# A-Main.net
KiCad netlist of a schematic drawn in Altium Designer
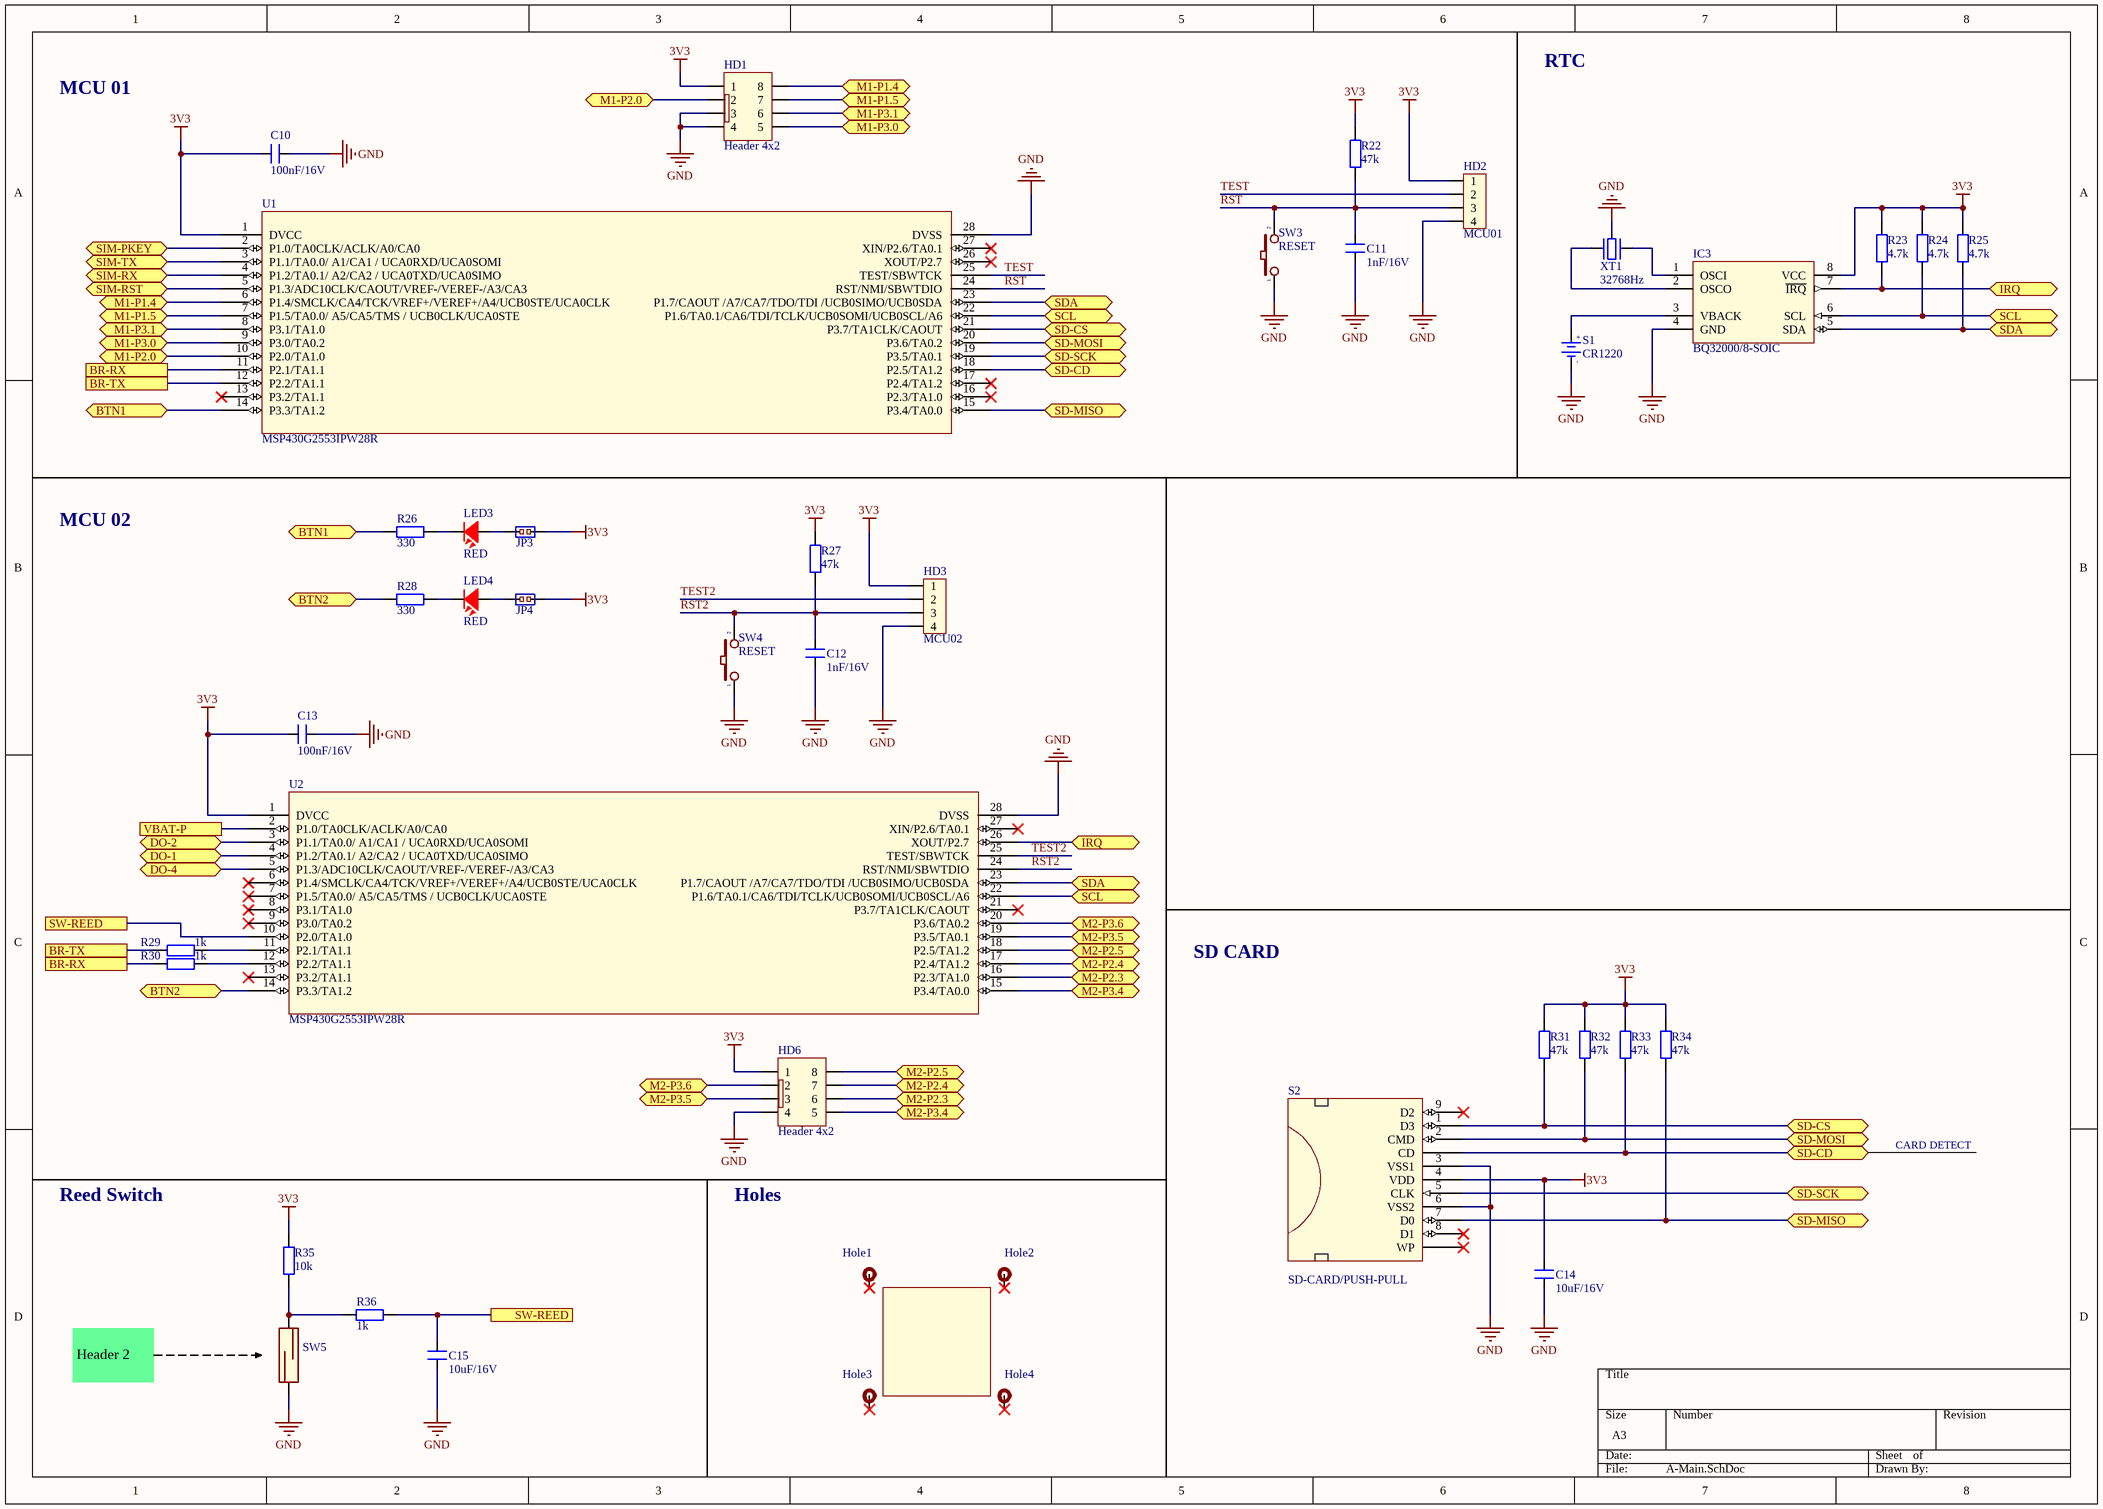
[diagram p0: A-Main.SchDoc]

(export (version "E")
  (design (tool "Eeschema 10.0.6"))
  (components
    (comp (ref "C10")
      (value "100nF/16V")
      (footprint "C0805-2012")
      (description "CAP CER 0.1UF 16V X7R 0805")
      (fields
        (field (name "MANUFACTURER") "Kemet")
        (field (name "MANUFACTURER PART NUMBER") "C0805C104K4RACTU")
      )
      (libsource (lib "Tran Tuan") (part "CAP-CER/100nF/16V/X7R/0805"))
    )
    (comp (ref "C11")
      (value "1nF/16V")
      (footprint "C0603-1608")
      (description "CAP CER 1000PF 16V X7R 0603")
      (fields
        (field (name "MANUFACTURER") "AVX Corporation")
        (field (name "MANUFACTURER PART NUMBER") "0603YC102KAT2A")
      )
      (libsource (lib "Tran Tuan") (part "CAP-CER/1nF/16V/X7R/0603"))
    )
    (comp (ref "C12")
      (value "1nF/16V")
      (footprint "C0603-1608")
      (description "CAP CER 1000PF 16V X7R 0603")
      (fields
        (field (name "MANUFACTURER") "AVX Corporation")
        (field (name "MANUFACTURER PART NUMBER") "0603YC102KAT2A")
      )
      (libsource (lib "Tran Tuan") (part "CAP-CER/1nF/16V/X7R/0603"))
    )
    (comp (ref "C13")
      (value "100nF/16V")
      (footprint "C0805-2012")
      (description "CAP CER 0.1UF 16V X7R 0805")
      (fields
        (field (name "MANUFACTURER") "Kemet")
        (field (name "MANUFACTURER PART NUMBER") "C0805C104K4RACTU")
      )
      (libsource (lib "Tran Tuan") (part "CAP-CER/100nF/16V/X7R/0805"))
    )
    (comp (ref "C14")
      (value "10uF/16V")
      (footprint "C0805-2012")
      (description "CAP CER 10UF 16V X5R 0805")
      (fields
        (field (name "MANUFACTURER") "Murata Electronics North America")
        (field (name "MANUFACTURER PART NUMBER") "GRM21BR61C106KE15L")
      )
      (libsource (lib "Tran Tuan") (part "CAP-CER/10UF/16V/X5R/0805"))
    )
    (comp (ref "C15")
      (value "10uF/16V")
      (footprint "C0805-2012")
      (description "CAP CER 10UF 16V X5R 0805")
      (fields
        (field (name "MANUFACTURER") "Murata Electronics North America")
        (field (name "MANUFACTURER PART NUMBER") "GRM21BR61C106KE15L")
      )
      (libsource (lib "Tran Tuan") (part "CAP-CER/10UF/16V/X5R/0805"))
    )
    (comp (ref "HD1")
      (value "Header 4x2")
      (footprint "HeaderSP_4x2")
      (description "HEADER, 4X2, 2.54MM, MALE")
      (libsource (lib "Tran Tuan") (part "HED-4X2/MALE/2.54MM-B"))
    )
    (comp (ref "HD2")
      (value "MCU01")
      (footprint "Header_4")
      (description "Header 4")
      (libsource (lib "Tran Tuan") (part "Hed4"))
    )
    (comp (ref "HD3")
      (value "MCU02")
      (footprint "Header_4")
      (description "Header 4")
      (libsource (lib "Tran Tuan") (part "Hed4"))
    )
    (comp (ref "HD6")
      (value "Header 4x2")
      (footprint "HeaderSP_4x2")
      (description "HEADER, 4X2, 2.54MM, MALE")
      (libsource (lib "Tran Tuan") (part "HED-4X2/MALE/2.54MM-B"))
    )
    (comp (ref "Hole1")
      (value "Pad Big")
      (footprint "Screw 3.0")
      (libsource (lib "Tran Tuan") (part "Pad_Big"))
    )
    (comp (ref "Hole2")
      (value "Pad Big")
      (footprint "Screw 3.0")
      (libsource (lib "Tran Tuan") (part "Pad_Big"))
    )
    (comp (ref "Hole3")
      (value "Pad Big")
      (footprint "Screw 3.0")
      (libsource (lib "Tran Tuan") (part "Pad_Big"))
    )
    (comp (ref "Hole4")
      (value "Pad Big")
      (footprint "Screw 3.0")
      (libsource (lib "Tran Tuan") (part "Pad_Big"))
    )
    (comp (ref "IC3")
      (value "BQ32000/8-SOIC")
      (footprint "RTC-BQ32000")
      (description "IC RTC CLK/CALENDAR I2C 8-SOIC")
      (fields
        (field (name "MANUFACTURER") "Texas Instruments")
        (field (name "MANUFACTURER PART NUMBER") "BQ32000DR")
      )
      (libsource (lib "Tran Tuan") (part "BQ32000/8-SOIC"))
    )
    (comp (ref "JP3")
      (value "JP2-ShortingJumper")
      (footprint "Header_2")
      (description "2.54mm 2-Pin Shorting Jumper")
      (libsource (lib "Tran Tuan") (part "JP2-ShortingJumper"))
    )
    (comp (ref "JP4")
      (value "JP2-ShortingJumper")
      (footprint "Header_2")
      (description "2.54mm 2-Pin Shorting Jumper")
      (libsource (lib "Tran Tuan") (part "JP2-ShortingJumper"))
    )
    (comp (ref "LED3")
      (value "RED")
      (footprint "Led 0805R")
      (description "LED RED CLEAR 0805 SMD")
      (fields
        (field (name "MANUFACTURER") "Lite-On Inc.")
        (field (name "MANUFACTURER PART NUMBER") "LTST-C171KRKT")
      )
      (libsource (lib "Tran Tuan") (part "LED-RED/CLEAR/0805"))
    )
    (comp (ref "LED4")
      (value "RED")
      (footprint "Led 0805R")
      (description "LED RED CLEAR 0805 SMD")
      (fields
        (field (name "MANUFACTURER") "Lite-On Inc.")
        (field (name "MANUFACTURER PART NUMBER") "LTST-C171KRKT")
      )
      (libsource (lib "Tran Tuan") (part "LED-RED/CLEAR/0805"))
    )
    (comp (ref "R22")
      (value "~")
      (footprint "RESC2012(0805)")
      (description "RES SMD 47K OHM 5% 1/8W 0805")
      (fields
        (field (name "MANUFACTURER") "Yageo")
        (field (name "MANUFACTURER PART NUMBER") "RC0805JR-0747KL")
        (field (name "RESISTANCE (OHMS)") "47k")
      )
      (libsource (lib "Tran Tuan") (part "RES-0805/±5%"))
    )
    (comp (ref "R23")
      (value "~")
      (footprint "RESC2012(0805)")
      (description "RES SMD 4.7K OHM 5% 1/8W 0805")
      (fields
        (field (name "MANUFACTURER") "Yageo")
        (field (name "MANUFACTURER PART NUMBER") "RC0805JR-074K7L")
        (field (name "RESISTANCE (OHMS)") "4.7k")
      )
      (libsource (lib "Tran Tuan") (part "RES-0805/±5%"))
    )
    (comp (ref "R24")
      (value "~")
      (footprint "RESC2012(0805)")
      (description "RES SMD 4.7K OHM 5% 1/8W 0805")
      (fields
        (field (name "MANUFACTURER") "Yageo")
        (field (name "MANUFACTURER PART NUMBER") "RC0805JR-074K7L")
        (field (name "RESISTANCE (OHMS)") "4.7k")
      )
      (libsource (lib "Tran Tuan") (part "RES-0805/±5%"))
    )
    (comp (ref "R25")
      (value "~")
      (footprint "RESC2012(0805)")
      (description "RES SMD 4.7K OHM 5% 1/8W 0805")
      (fields
        (field (name "MANUFACTURER") "Yageo")
        (field (name "MANUFACTURER PART NUMBER") "RC0805JR-074K7L")
        (field (name "RESISTANCE (OHMS)") "4.7k")
      )
      (libsource (lib "Tran Tuan") (part "RES-0805/±5%"))
    )
    (comp (ref "R26")
      (value "~")
      (footprint "RESC2012(0805)")
      (description "RES SMD 330 OHM 5% 1/8W 0805")
      (fields
        (field (name "MANUFACTURER") "Yageo")
        (field (name "MANUFACTURER PART NUMBER") "RC0805JR-07330RL")
        (field (name "RESISTANCE (OHMS)") "330")
      )
      (libsource (lib "") (part "RES-0805/±5%_1"))
    )
    (comp (ref "R27")
      (value "~")
      (footprint "RESC2012(0805)")
      (description "RES SMD 47K OHM 5% 1/8W 0805")
      (fields
        (field (name "MANUFACTURER") "Yageo")
        (field (name "MANUFACTURER PART NUMBER") "RC0805JR-0747KL")
        (field (name "RESISTANCE (OHMS)") "47k")
      )
      (libsource (lib "Tran Tuan") (part "RES-0805/±5%"))
    )
    (comp (ref "R28")
      (value "~")
      (footprint "RESC2012(0805)")
      (description "RES SMD 330 OHM 5% 1/8W 0805")
      (fields
        (field (name "MANUFACTURER") "Yageo")
        (field (name "MANUFACTURER PART NUMBER") "RC0805JR-07330RL")
        (field (name "RESISTANCE (OHMS)") "330")
      )
      (libsource (lib "") (part "RES-0805/±5%_1"))
    )
    (comp (ref "R29")
      (value "~")
      (footprint "RESC2012(0805)")
      (description "RES SMD 1K OHM 5% 1/8W 0805")
      (fields
        (field (name "MANUFACTURER") "Yageo")
        (field (name "MANUFACTURER PART NUMBER") "RC0805JR-071KL")
        (field (name "RESISTANCE (OHMS)") "1k")
      )
      (libsource (lib "") (part "RES-0805/±5%_1"))
    )
    (comp (ref "R30")
      (value "~")
      (footprint "RESC2012(0805)")
      (description "RES SMD 1K OHM 5% 1/8W 0805")
      (fields
        (field (name "MANUFACTURER") "Yageo")
        (field (name "MANUFACTURER PART NUMBER") "RC0805JR-071KL")
        (field (name "RESISTANCE (OHMS)") "1k")
      )
      (libsource (lib "") (part "RES-0805/±5%_1"))
    )
    (comp (ref "R31")
      (value "~")
      (footprint "RESC2012(0805)")
      (description "RES SMD 47K OHM 5% 1/8W 0805")
      (fields
        (field (name "MANUFACTURER") "Yageo")
        (field (name "MANUFACTURER PART NUMBER") "RC0805JR-0747KL")
        (field (name "RESISTANCE (OHMS)") "47k")
      )
      (libsource (lib "Tran Tuan") (part "RES-0805/±5%"))
    )
    (comp (ref "R32")
      (value "~")
      (footprint "RESC2012(0805)")
      (description "RES SMD 47K OHM 5% 1/8W 0805")
      (fields
        (field (name "MANUFACTURER") "Yageo")
        (field (name "MANUFACTURER PART NUMBER") "RC0805JR-0747KL")
        (field (name "RESISTANCE (OHMS)") "47k")
      )
      (libsource (lib "Tran Tuan") (part "RES-0805/±5%"))
    )
    (comp (ref "R33")
      (value "~")
      (footprint "RESC2012(0805)")
      (description "RES SMD 47K OHM 5% 1/8W 0805")
      (fields
        (field (name "MANUFACTURER") "Yageo")
        (field (name "MANUFACTURER PART NUMBER") "RC0805JR-0747KL")
        (field (name "RESISTANCE (OHMS)") "47k")
      )
      (libsource (lib "Tran Tuan") (part "RES-0805/±5%"))
    )
    (comp (ref "R34")
      (value "~")
      (footprint "RESC2012(0805)")
      (description "RES SMD 47K OHM 5% 1/8W 0805")
      (fields
        (field (name "MANUFACTURER") "Yageo")
        (field (name "MANUFACTURER PART NUMBER") "RC0805JR-0747KL")
        (field (name "RESISTANCE (OHMS)") "47k")
      )
      (libsource (lib "Tran Tuan") (part "RES-0805/±5%"))
    )
    (comp (ref "R35")
      (value "~")
      (footprint "RESC2012(0805)")
      (description "RES SMD 10K OHM 5% 1/8W 0805")
      (fields
        (field (name "MANUFACTURER") "Yageo")
        (field (name "MANUFACTURER PART NUMBER") "RC0805JR-0710KL")
        (field (name "RESISTANCE (OHMS)") "10k")
      )
      (libsource (lib "") (part "RES-0805/±5%_2"))
    )
    (comp (ref "R36")
      (value "~")
      (footprint "RESC2012(0805)")
      (description "RES SMD 1K OHM 5% 1/8W 0805")
      (fields
        (field (name "MANUFACTURER") "Yageo")
        (field (name "MANUFACTURER PART NUMBER") "RC0805JR-071KL")
        (field (name "RESISTANCE (OHMS)") "1k")
      )
      (libsource (lib "") (part "RES-0805/±5%_1"))
    )
    (comp (ref "S1")
      (value "CR1220")
      (footprint "Socket-PIN-BC501SM-TR")
      (description "CR1220 Battery Holder SMD")
      (fields (field (name "Comment") "BAT-HOLDER/CR1220/TME"))
      (libsource (lib "Tran Tuan") (part "BAT-HOLDER/CR1220/TME"))
    )
    (comp (ref "S2")
      (value "SD-CARD/PUSH-PULL")
      (footprint "SD-CARD")
      (description "CONN SD CARD PUSH-PUSH R/A SMD")
      (fields
        (field (name "MANUFACTURER") "Amphenol Commercial Products")
        (field (name "MANUFACTURER PART NUMBER") "101-00313-68-02")
      )
      (libsource (lib "Tran Tuan") (part "SD-CARD/PUSH-PULL"))
    )
    (comp (ref "SW3")
      (value "RESET")
      (footprint "BTN-EVQ-11A04M")
      (description "SWITCH TACTILE SPST-NO 0.02A 15V")
      (fields
        (field (name "MANUFACTURER") "Panasonic Electronic Components")
        (field (name "MANUFACTURER PART NUMBER") "EVQ-11A04M")
      )
      (libsource (lib "Tran Tuan") (part "SW2-PUSH/SPST/NO"))
    )
    (comp (ref "SW4")
      (value "RESET")
      (footprint "BTN-EVQ-11A04M")
      (description "SWITCH TACTILE SPST-NO 0.02A 15V")
      (fields
        (field (name "MANUFACTURER") "Panasonic Electronic Components")
        (field (name "MANUFACTURER PART NUMBER") "EVQ-11A04M")
      )
      (libsource (lib "Tran Tuan") (part "SW2-PUSH/SPST/NO"))
    )
    (comp (ref "SW5")
      (value "SW-REED/SPST/NO/350mA")
      (footprint "SWITCH-SDSM")
      (description "SWITCH REED SPST-NO 350MA 140V")
      (fields
        (field (name "MANUFACTURER") "Littelfuse Inc.")
        (field (name "MANUFACTURER PART NUMBER") "MDSM-4R-12-18")
      )
      (libsource (lib "Tran Tuan") (part "SW-REED/SPST/NO/350mA"))
    )
    (comp (ref "U1")
      (value "MSP430G2553IPW28R")
      (footprint "MSP430G2253IPW28R")
      (description "IC MCU 16BIT 16KB FLASH 28TSSOP")
      (fields (field (name "MANUFACTURER") "Texas Instruments"))
      (libsource (lib "Tran Tuan") (part "MSP430G2553IPW28R"))
    )
    (comp (ref "U2")
      (value "MSP430G2553IPW28R")
      (footprint "MSP430G2253IPW28R")
      (description "IC MCU 16BIT 16KB FLASH 28TSSOP")
      (fields (field (name "MANUFACTURER") "Texas Instruments"))
      (libsource (lib "Tran Tuan") (part "MSP430G2553IPW28R"))
    )
    (comp (ref "XT1")
      (value "32768Hz")
      (footprint "CR_32768")
      (description "CRYSTAL 32.7680KHZ 12.5PF T/H")
      (fields
        (field (name "MANUFACTURER") "Citizen Finedevice Co Ltd")
        (field (name "MANUFACTURER PART NUMBER") "CFS206-32.768KDZF-UB")
      )
      (libsource (lib "Tran Tuan") (part "XT-32768HZ/RADIAL"))
    )
  )
  (nets
    (net (code "1") (name "/BR-RX") (class "Default")
      (node (ref "R30") (pin "2") (pinfunction "2_2") (pintype "passive"))
      (node (ref "U1") (pin "11") (pinfunction "P2.1/TA1.1_11") (pintype "bidirectional"))
    )
    (net (code "2") (name "/BR-TX") (class "Default")
      (node (ref "R29") (pin "2") (pinfunction "2_2") (pintype "passive"))
      (node (ref "U1") (pin "12") (pinfunction "P2.2/TA1.1_12") (pintype "bidirectional"))
    )
    (net (code "3") (name "/BTN1") (class "Default")
      (node (ref "R26") (pin "2") (pinfunction "2_2") (pintype "passive"))
      (node (ref "U1") (pin "14") (pinfunction "P3.3/TA1.2_14") (pintype "bidirectional"))
    )
    (net (code "4") (name "/BTN2") (class "Default")
      (node (ref "R28") (pin "2") (pinfunction "2_2") (pintype "passive"))
      (node (ref "U2") (pin "14") (pinfunction "P3.3/TA1.2_14") (pintype "bidirectional"))
    )
    (net (code "5") (name "/DO-1") (class "Default")
      (node (ref "U2") (pin "4") (pinfunction "P1.2/TA0.1/_A2/CA2_/_UCA0TXD/UCA0SIMO_4") (pintype "bidirectional"))
    )
    (net (code "6") (name "/DO-2") (class "Default")
      (node (ref "U2") (pin "3") (pinfunction "P1.1/TA0.0/_A1/CA1_/_UCA0RXD/UCA0SOMI_3") (pintype "bidirectional"))
    )
    (net (code "7") (name "/DO-4") (class "Default")
      (node (ref "U2") (pin "5") (pinfunction "P1.3/ADC10CLK/CAOUT/VREF-/VEREF-/A3/CA3_5") (pintype "bidirectional"))
    )
    (net (code "8") (name "/IRQ") (class "Default")
      (node (ref "IC3") (pin "7") (pinfunction "~{IRQ}_7") (pintype "output"))
      (node (ref "R23") (pin "1") (pinfunction "1_1") (pintype "passive"))
      (node (ref "U2") (pin "26") (pinfunction "XOUT/P2.7_26") (pintype "bidirectional"))
    )
    (net (code "9") (name "/M1-P1.4") (class "Default")
      (node (ref "HD1") (pin "8") (pinfunction "8_8") (pintype "passive"))
      (node (ref "U1") (pin "6") (pinfunction "P1.4/SMCLK/CA4/TCK/VREF+/VEREF+/A4/UCB0STE/UCA0CLK_6") (pintype "bidirectional"))
    )
    (net (code "10") (name "/M1-P1.5") (class "Default")
      (node (ref "HD1") (pin "7") (pinfunction "7_7") (pintype "passive"))
      (node (ref "U1") (pin "7") (pinfunction "P1.5/TA0.0/_A5/CA5/TMS_/_UCB0CLK/UCA0STE_7") (pintype "bidirectional"))
    )
    (net (code "11") (name "/M1-P2.0") (class "Default")
      (node (ref "HD1") (pin "2") (pinfunction "2_2") (pintype "passive"))
      (node (ref "U1") (pin "10") (pinfunction "P2.0/TA1.0_10") (pintype "bidirectional"))
    )
    (net (code "12") (name "/M1-P3.0") (class "Default")
      (node (ref "HD1") (pin "5") (pinfunction "5_5") (pintype "passive"))
      (node (ref "U1") (pin "9") (pinfunction "P3.0/TA0.2_9") (pintype "bidirectional"))
    )
    (net (code "13") (name "/M1-P3.1") (class "Default")
      (node (ref "HD1") (pin "6") (pinfunction "6_6") (pintype "passive"))
      (node (ref "U1") (pin "8") (pinfunction "P3.1/TA1.0_8") (pintype "bidirectional"))
    )
    (net (code "14") (name "/M2-P2.3") (class "Default")
      (node (ref "HD6") (pin "6") (pinfunction "6_6") (pintype "passive"))
      (node (ref "U2") (pin "16") (pinfunction "P2.3/TA1.0_16") (pintype "bidirectional"))
    )
    (net (code "15") (name "/M2-P2.4") (class "Default")
      (node (ref "HD6") (pin "7") (pinfunction "7_7") (pintype "passive"))
      (node (ref "U2") (pin "17") (pinfunction "P2.4/TA1.2_17") (pintype "bidirectional"))
    )
    (net (code "16") (name "/M2-P2.5") (class "Default")
      (node (ref "HD6") (pin "8") (pinfunction "8_8") (pintype "passive"))
      (node (ref "U2") (pin "18") (pinfunction "P2.5/TA1.2_18") (pintype "bidirectional"))
    )
    (net (code "17") (name "/M2-P3.4") (class "Default")
      (node (ref "HD6") (pin "5") (pinfunction "5_5") (pintype "passive"))
      (node (ref "U2") (pin "15") (pinfunction "P3.4/TA0.0_15") (pintype "bidirectional"))
    )
    (net (code "18") (name "/M2-P3.5") (class "Default")
      (node (ref "HD6") (pin "3") (pinfunction "3_3") (pintype "passive"))
      (node (ref "U2") (pin "19") (pinfunction "P3.5/TA0.1_19") (pintype "bidirectional"))
    )
    (net (code "19") (name "/M2-P3.6") (class "Default")
      (node (ref "HD6") (pin "2") (pinfunction "2_2") (pintype "passive"))
      (node (ref "U2") (pin "20") (pinfunction "P3.6/TA0.2_20") (pintype "bidirectional"))
    )
    (net (code "20") (name "/RST") (class "Default")
      (node (ref "C11") (pin "1") (pinfunction "1_1") (pintype "passive"))
      (node (ref "HD2") (pin "3") (pinfunction "3_3") (pintype "passive"))
      (node (ref "R22") (pin "1") (pinfunction "1_1") (pintype "passive"))
      (node (ref "SW3") (pin "2") (pinfunction "2_2") (pintype "passive"))
      (node (ref "U1") (pin "24") (pinfunction "RST/NMI/SBWTDIO_24") (pintype "passive"))
    )
    (net (code "21") (name "/RST2") (class "Default")
      (node (ref "C12") (pin "1") (pinfunction "1_1") (pintype "passive"))
      (node (ref "HD3") (pin "3") (pinfunction "3_3") (pintype "passive"))
      (node (ref "R27") (pin "1") (pinfunction "1_1") (pintype "passive"))
      (node (ref "SW4") (pin "2") (pinfunction "2_2") (pintype "passive"))
      (node (ref "U2") (pin "24") (pinfunction "RST/NMI/SBWTDIO_24") (pintype "passive"))
    )
    (net (code "22") (name "/SCL") (class "Default")
      (node (ref "IC3") (pin "6") (pinfunction "SCL_6") (pintype "input"))
      (node (ref "R24") (pin "1") (pinfunction "1_1") (pintype "passive"))
      (node (ref "U1") (pin "22") (pinfunction "P1.6/TA0.1/CA6/TDI/TCLK/UCB0SOMI/UCB0SCL/A6_22") (pintype "bidirectional"))
      (node (ref "U2") (pin "22") (pinfunction "P1.6/TA0.1/CA6/TDI/TCLK/UCB0SOMI/UCB0SCL/A6_22") (pintype "bidirectional"))
    )
    (net (code "23") (name "/SD-CD") (class "Default")
      (node (ref "R33") (pin "1") (pinfunction "1_1") (pintype "passive"))
      (node (ref "S2") (pin "CD") (pinfunction "CD_CD") (pintype "passive"))
      (node (ref "U1") (pin "18") (pinfunction "P2.5/TA1.2_18") (pintype "bidirectional"))
    )
    (net (code "24") (name "/SD-CS") (class "Default")
      (node (ref "R31") (pin "1") (pinfunction "1_1") (pintype "passive"))
      (node (ref "S2") (pin "1") (pinfunction "D3_1") (pintype "bidirectional"))
      (node (ref "U1") (pin "21") (pinfunction "P3.7/TA1CLK/CAOUT_21") (pintype "bidirectional"))
    )
    (net (code "25") (name "/SD-MISO") (class "Default")
      (node (ref "R34") (pin "1") (pinfunction "1_1") (pintype "passive"))
      (node (ref "S2") (pin "7") (pinfunction "D0_7") (pintype "bidirectional"))
      (node (ref "U1") (pin "15") (pinfunction "P3.4/TA0.0_15") (pintype "bidirectional"))
    )
    (net (code "26") (name "/SD-MOSI") (class "Default")
      (node (ref "R32") (pin "1") (pinfunction "1_1") (pintype "passive"))
      (node (ref "S2") (pin "2") (pinfunction "CMD_2") (pintype "bidirectional"))
      (node (ref "U1") (pin "20") (pinfunction "P3.6/TA0.2_20") (pintype "bidirectional"))
    )
    (net (code "27") (name "/SD-SCK") (class "Default")
      (node (ref "S2") (pin "5") (pinfunction "CLK_5") (pintype "input"))
      (node (ref "U1") (pin "19") (pinfunction "P3.5/TA0.1_19") (pintype "bidirectional"))
    )
    (net (code "28") (name "/SDA") (class "Default")
      (node (ref "IC3") (pin "5") (pinfunction "SDA_5") (pintype "bidirectional"))
      (node (ref "R25") (pin "1") (pinfunction "1_1") (pintype "passive"))
      (node (ref "U1") (pin "23") (pinfunction "P1.7/CAOUT_/A7/CA7/TDO/TDI_/UCB0SIMO/UCB0SDA_23") (pintype "bidirectional"))
      (node (ref "U2") (pin "23") (pinfunction "P1.7/CAOUT_/A7/CA7/TDO/TDI_/UCB0SIMO/UCB0SDA_23") (pintype "bidirectional"))
    )
    (net (code "29") (name "/SIM-PKEY") (class "Default")
      (node (ref "U1") (pin "2") (pinfunction "P1.0/TA0CLK/ACLK/A0/CA0_2") (pintype "bidirectional"))
    )
    (net (code "30") (name "/SIM-RST") (class "Default")
      (node (ref "U1") (pin "5") (pinfunction "P1.3/ADC10CLK/CAOUT/VREF-/VEREF-/A3/CA3_5") (pintype "bidirectional"))
    )
    (net (code "31") (name "/SIM-RX") (class "Default")
      (node (ref "U1") (pin "4") (pinfunction "P1.2/TA0.1/_A2/CA2_/_UCA0TXD/UCA0SIMO_4") (pintype "bidirectional"))
    )
    (net (code "32") (name "/SIM-TX") (class "Default")
      (node (ref "U1") (pin "3") (pinfunction "P1.1/TA0.0/_A1/CA1_/_UCA0RXD/UCA0SOMI_3") (pintype "bidirectional"))
    )
    (net (code "33") (name "/SW-REED") (class "Default")
      (node (ref "C15") (pin "1") (pinfunction "1_1") (pintype "passive"))
      (node (ref "R36") (pin "1") (pinfunction "1_1") (pintype "passive"))
      (node (ref "U2") (pin "10") (pinfunction "P2.0/TA1.0_10") (pintype "bidirectional"))
    )
    (net (code "34") (name "/TEST") (class "Default")
      (node (ref "HD2") (pin "2") (pinfunction "2_2") (pintype "passive"))
      (node (ref "U1") (pin "25") (pinfunction "TEST/SBWTCK_25") (pintype "passive"))
    )
    (net (code "35") (name "/TEST2") (class "Default")
      (node (ref "HD3") (pin "2") (pinfunction "2_2") (pintype "passive"))
      (node (ref "U2") (pin "25") (pinfunction "TEST/SBWTCK_25") (pintype "passive"))
    )
    (net (code "36") (name "/VBAT-P") (class "Default")
      (node (ref "U2") (pin "2") (pinfunction "P1.0/TA0CLK/ACLK/A0/CA0_2") (pintype "bidirectional"))
    )
    (net (code "37") (name "3V3") (class "Default")
      (node (ref "C10") (pin "1") (pinfunction "1_1") (pintype "passive"))
      (node (ref "C13") (pin "1") (pinfunction "1_1") (pintype "passive"))
      (node (ref "C14") (pin "1") (pinfunction "1_1") (pintype "passive"))
      (node (ref "HD1") (pin "1") (pinfunction "1_1") (pintype "passive"))
      (node (ref "HD2") (pin "1") (pinfunction "1_1") (pintype "passive"))
      (node (ref "HD3") (pin "1") (pinfunction "1_1") (pintype "passive"))
      (node (ref "HD6") (pin "1") (pinfunction "1_1") (pintype "passive"))
      (node (ref "IC3") (pin "8") (pinfunction "VCC_8") (pintype "power_in"))
      (node (ref "JP3") (pin "2") (pinfunction "2_2") (pintype "passive"))
      (node (ref "JP4") (pin "2") (pinfunction "2_2") (pintype "passive"))
      (node (ref "R22") (pin "2") (pinfunction "2_2") (pintype "passive"))
      (node (ref "R23") (pin "2") (pinfunction "2_2") (pintype "passive"))
      (node (ref "R24") (pin "2") (pinfunction "2_2") (pintype "passive"))
      (node (ref "R25") (pin "2") (pinfunction "2_2") (pintype "passive"))
      (node (ref "R27") (pin "2") (pinfunction "2_2") (pintype "passive"))
      (node (ref "R31") (pin "2") (pinfunction "2_2") (pintype "passive"))
      (node (ref "R32") (pin "2") (pinfunction "2_2") (pintype "passive"))
      (node (ref "R33") (pin "2") (pinfunction "2_2") (pintype "passive"))
      (node (ref "R34") (pin "2") (pinfunction "2_2") (pintype "passive"))
      (node (ref "R35") (pin "1") (pinfunction "1_1") (pintype "passive"))
      (node (ref "S2") (pin "4") (pinfunction "VDD_4") (pintype "power_in"))
      (node (ref "U1") (pin "1") (pinfunction "DVCC_1") (pintype "power_in"))
      (node (ref "U2") (pin "1") (pinfunction "DVCC_1") (pintype "power_in"))
    )
    (net (code "38") (name "GND") (class "Default")
      (node (ref "C10") (pin "2") (pinfunction "2_2") (pintype "passive"))
      (node (ref "C11") (pin "2") (pinfunction "2_2") (pintype "passive"))
      (node (ref "C12") (pin "2") (pinfunction "2_2") (pintype "passive"))
      (node (ref "C13") (pin "2") (pinfunction "2_2") (pintype "passive"))
      (node (ref "C14") (pin "2") (pinfunction "2_2") (pintype "passive"))
      (node (ref "C15") (pin "2") (pinfunction "2_2") (pintype "passive"))
      (node (ref "HD1") (pin "3") (pinfunction "3_3") (pintype "passive"))
      (node (ref "HD1") (pin "4") (pinfunction "4_4") (pintype "passive"))
      (node (ref "HD2") (pin "4") (pinfunction "4_4") (pintype "passive"))
      (node (ref "HD3") (pin "4") (pinfunction "4_4") (pintype "passive"))
      (node (ref "HD6") (pin "4") (pinfunction "4_4") (pintype "passive"))
      (node (ref "IC3") (pin "4") (pinfunction "GND_4") (pintype "power_in"))
      (node (ref "S1") (pin "2") (pinfunction "GND_2") (pintype "passive"))
      (node (ref "S2") (pin "3") (pinfunction "VSS1_3") (pintype "power_in"))
      (node (ref "S2") (pin "6") (pinfunction "VSS2_6") (pintype "power_in"))
      (node (ref "SW3") (pin "1") (pinfunction "1_1") (pintype "passive"))
      (node (ref "SW4") (pin "1") (pinfunction "1_1") (pintype "passive"))
      (node (ref "SW5") (pin "1") (pinfunction "1_1") (pintype "passive"))
      (node (ref "U1") (pin "28") (pinfunction "DVSS_28") (pintype "passive"))
      (node (ref "U2") (pin "28") (pinfunction "DVSS_28") (pintype "passive"))
      (node (ref "XT1") (pin "0") (pinfunction "Case_0") (pintype "passive"))
    )
    (net (code "39") (name "Net-(IC3-OSCI)") (class "Default")
      (node (ref "IC3") (pin "1") (pinfunction "OSCI_1") (pintype "passive"))
      (node (ref "XT1") (pin "2") (pinfunction "2_2") (pintype "passive"))
    )
    (net (code "40") (name "Net-(IC3-OSCO)") (class "Default")
      (node (ref "IC3") (pin "2") (pinfunction "OSCO_2") (pintype "passive"))
      (node (ref "XT1") (pin "1") (pinfunction "1_1") (pintype "passive"))
    )
    (net (code "41") (name "Net-(IC3-VBACK)") (class "Default")
      (node (ref "IC3") (pin "3") (pinfunction "VBACK_3") (pintype "power_in"))
      (node (ref "S1") (pin "1") (pinfunction "+3V_1") (pintype "passive"))
    )
    (net (code "42") (name "Net-(LED3-A)") (class "Default")
      (node (ref "JP3") (pin "1") (pinfunction "1_1") (pintype "passive"))
      (node (ref "LED3") (pin "1") (pinfunction "A_1") (pintype "passive"))
    )
    (net (code "43") (name "Net-(LED3-K)") (class "Default")
      (node (ref "LED3") (pin "2") (pinfunction "K_2") (pintype "passive"))
      (node (ref "R26") (pin "1") (pinfunction "1_1") (pintype "passive"))
    )
    (net (code "44") (name "Net-(LED4-A)") (class "Default")
      (node (ref "JP4") (pin "1") (pinfunction "1_1") (pintype "passive"))
      (node (ref "LED4") (pin "1") (pinfunction "A_1") (pintype "passive"))
    )
    (net (code "45") (name "Net-(LED4-K)") (class "Default")
      (node (ref "LED4") (pin "2") (pinfunction "K_2") (pintype "passive"))
      (node (ref "R28") (pin "1") (pinfunction "1_1") (pintype "passive"))
    )
    (net (code "46") (name "Net-(R35-Pad2)") (class "Default")
      (node (ref "R35") (pin "2") (pinfunction "2_2") (pintype "passive"))
      (node (ref "R36") (pin "2") (pinfunction "2_2") (pintype "passive"))
      (node (ref "SW5") (pin "2") (pinfunction "2_2") (pintype "passive"))
    )
    (net (code "47") (name "Net-(U2-P2.1{slash}TA1.1)") (class "Default")
      (node (ref "R29") (pin "1") (pinfunction "1_1") (pintype "passive"))
      (node (ref "U2") (pin "11") (pinfunction "P2.1/TA1.1_11") (pintype "bidirectional"))
    )
    (net (code "48") (name "Net-(U2-P2.2{slash}TA1.1)") (class "Default")
      (node (ref "R30") (pin "1") (pinfunction "1_1") (pintype "passive"))
      (node (ref "U2") (pin "12") (pinfunction "P2.2/TA1.1_12") (pintype "bidirectional"))
    )
    (net (code "49") (name "unconnected-(Hole1-Pad1)") (class "Default")
      (node (ref "Hole1") (pin "1") (pinfunction "1_1") (pintype "passive+no_connect"))
    )
    (net (code "50") (name "unconnected-(Hole2-Pad1)") (class "Default")
      (node (ref "Hole2") (pin "1") (pinfunction "1_1") (pintype "passive+no_connect"))
    )
    (net (code "51") (name "unconnected-(Hole3-Pad1)") (class "Default")
      (node (ref "Hole3") (pin "1") (pinfunction "1_1") (pintype "passive+no_connect"))
    )
    (net (code "52") (name "unconnected-(Hole4-Pad1)") (class "Default")
      (node (ref "Hole4") (pin "1") (pinfunction "1_1") (pintype "passive+no_connect"))
    )
    (net (code "53") (name "unconnected-(S2-D1-Pad8)") (class "Default")
      (node (ref "S2") (pin "8") (pinfunction "D1_8") (pintype "bidirectional+no_connect"))
    )
    (net (code "54") (name "unconnected-(S2-D2-Pad9)") (class "Default")
      (node (ref "S2") (pin "9") (pinfunction "D2_9") (pintype "bidirectional+no_connect"))
    )
    (net (code "55") (name "unconnected-(S2-PadWP)") (class "Default")
      (node (ref "S2") (pin "WP") (pinfunction "WP_WP") (pintype "passive+no_connect"))
    )
    (net (code "56") (name "unconnected-(U1-P2.3{slash}TA1.0-Pad16)") (class "Default")
      (node (ref "U1") (pin "16") (pinfunction "P2.3/TA1.0_16") (pintype "bidirectional+no_connect"))
    )
    (net (code "57") (name "unconnected-(U1-P2.4{slash}TA1.2-Pad17)") (class "Default")
      (node (ref "U1") (pin "17") (pinfunction "P2.4/TA1.2_17") (pintype "bidirectional+no_connect"))
    )
    (net (code "58") (name "unconnected-(U1-P3.2{slash}TA1.1-Pad13)") (class "Default")
      (node (ref "U1") (pin "13") (pinfunction "P3.2/TA1.1_13") (pintype "bidirectional+no_connect"))
    )
    (net (code "59") (name "unconnected-(U1-XIN{slash}P2.6{slash}TA0.1-Pad27)") (class "Default")
      (node (ref "U1") (pin "27") (pinfunction "XIN/P2.6/TA0.1_27") (pintype "bidirectional+no_connect"))
    )
    (net (code "60") (name "unconnected-(U1-XOUT{slash}P2.7-Pad26)") (class "Default")
      (node (ref "U1") (pin "26") (pinfunction "XOUT/P2.7_26") (pintype "bidirectional+no_connect"))
    )
    (net (code "61") (name "unconnected-(U2-P1.4{slash}SMCLK{slash}CA4{slash}TCK{slash}VREF+{slash}VEREF+{slash}A4{slash}UCB0STE{slash}UCA0CLK-Pad6)") (class "Default")
      (node (ref "U2") (pin "6") (pinfunction "P1.4/SMCLK/CA4/TCK/VREF+/VEREF+/A4/UCB0STE/UCA0CLK_6") (pintype "bidirectional+no_connect"))
    )
    (net (code "62") (name "unconnected-(U2-P1.5{slash}TA0.0{slash}_A5{slash}CA5{slash}TMS_{slash}_UCB0CLK{slash}UCA0STE-Pad7)") (class "Default")
      (node (ref "U2") (pin "7") (pinfunction "P1.5/TA0.0/_A5/CA5/TMS_/_UCB0CLK/UCA0STE_7") (pintype "bidirectional+no_connect"))
    )
    (net (code "63") (name "unconnected-(U2-P3.0{slash}TA0.2-Pad9)") (class "Default")
      (node (ref "U2") (pin "9") (pinfunction "P3.0/TA0.2_9") (pintype "bidirectional+no_connect"))
    )
    (net (code "64") (name "unconnected-(U2-P3.1{slash}TA1.0-Pad8)") (class "Default")
      (node (ref "U2") (pin "8") (pinfunction "P3.1/TA1.0_8") (pintype "bidirectional+no_connect"))
    )
    (net (code "65") (name "unconnected-(U2-P3.2{slash}TA1.1-Pad13)") (class "Default")
      (node (ref "U2") (pin "13") (pinfunction "P3.2/TA1.1_13") (pintype "bidirectional+no_connect"))
    )
    (net (code "66") (name "unconnected-(U2-P3.7{slash}TA1CLK{slash}CAOUT-Pad21)") (class "Default")
      (node (ref "U2") (pin "21") (pinfunction "P3.7/TA1CLK/CAOUT_21") (pintype "bidirectional+no_connect"))
    )
    (net (code "67") (name "unconnected-(U2-XIN{slash}P2.6{slash}TA0.1-Pad27)") (class "Default")
      (node (ref "U2") (pin "27") (pinfunction "XIN/P2.6/TA0.1_27") (pintype "bidirectional+no_connect"))
    )
  )
)
